# NixieClock.net
KiCad netlist of a schematic drawn in EAGLE
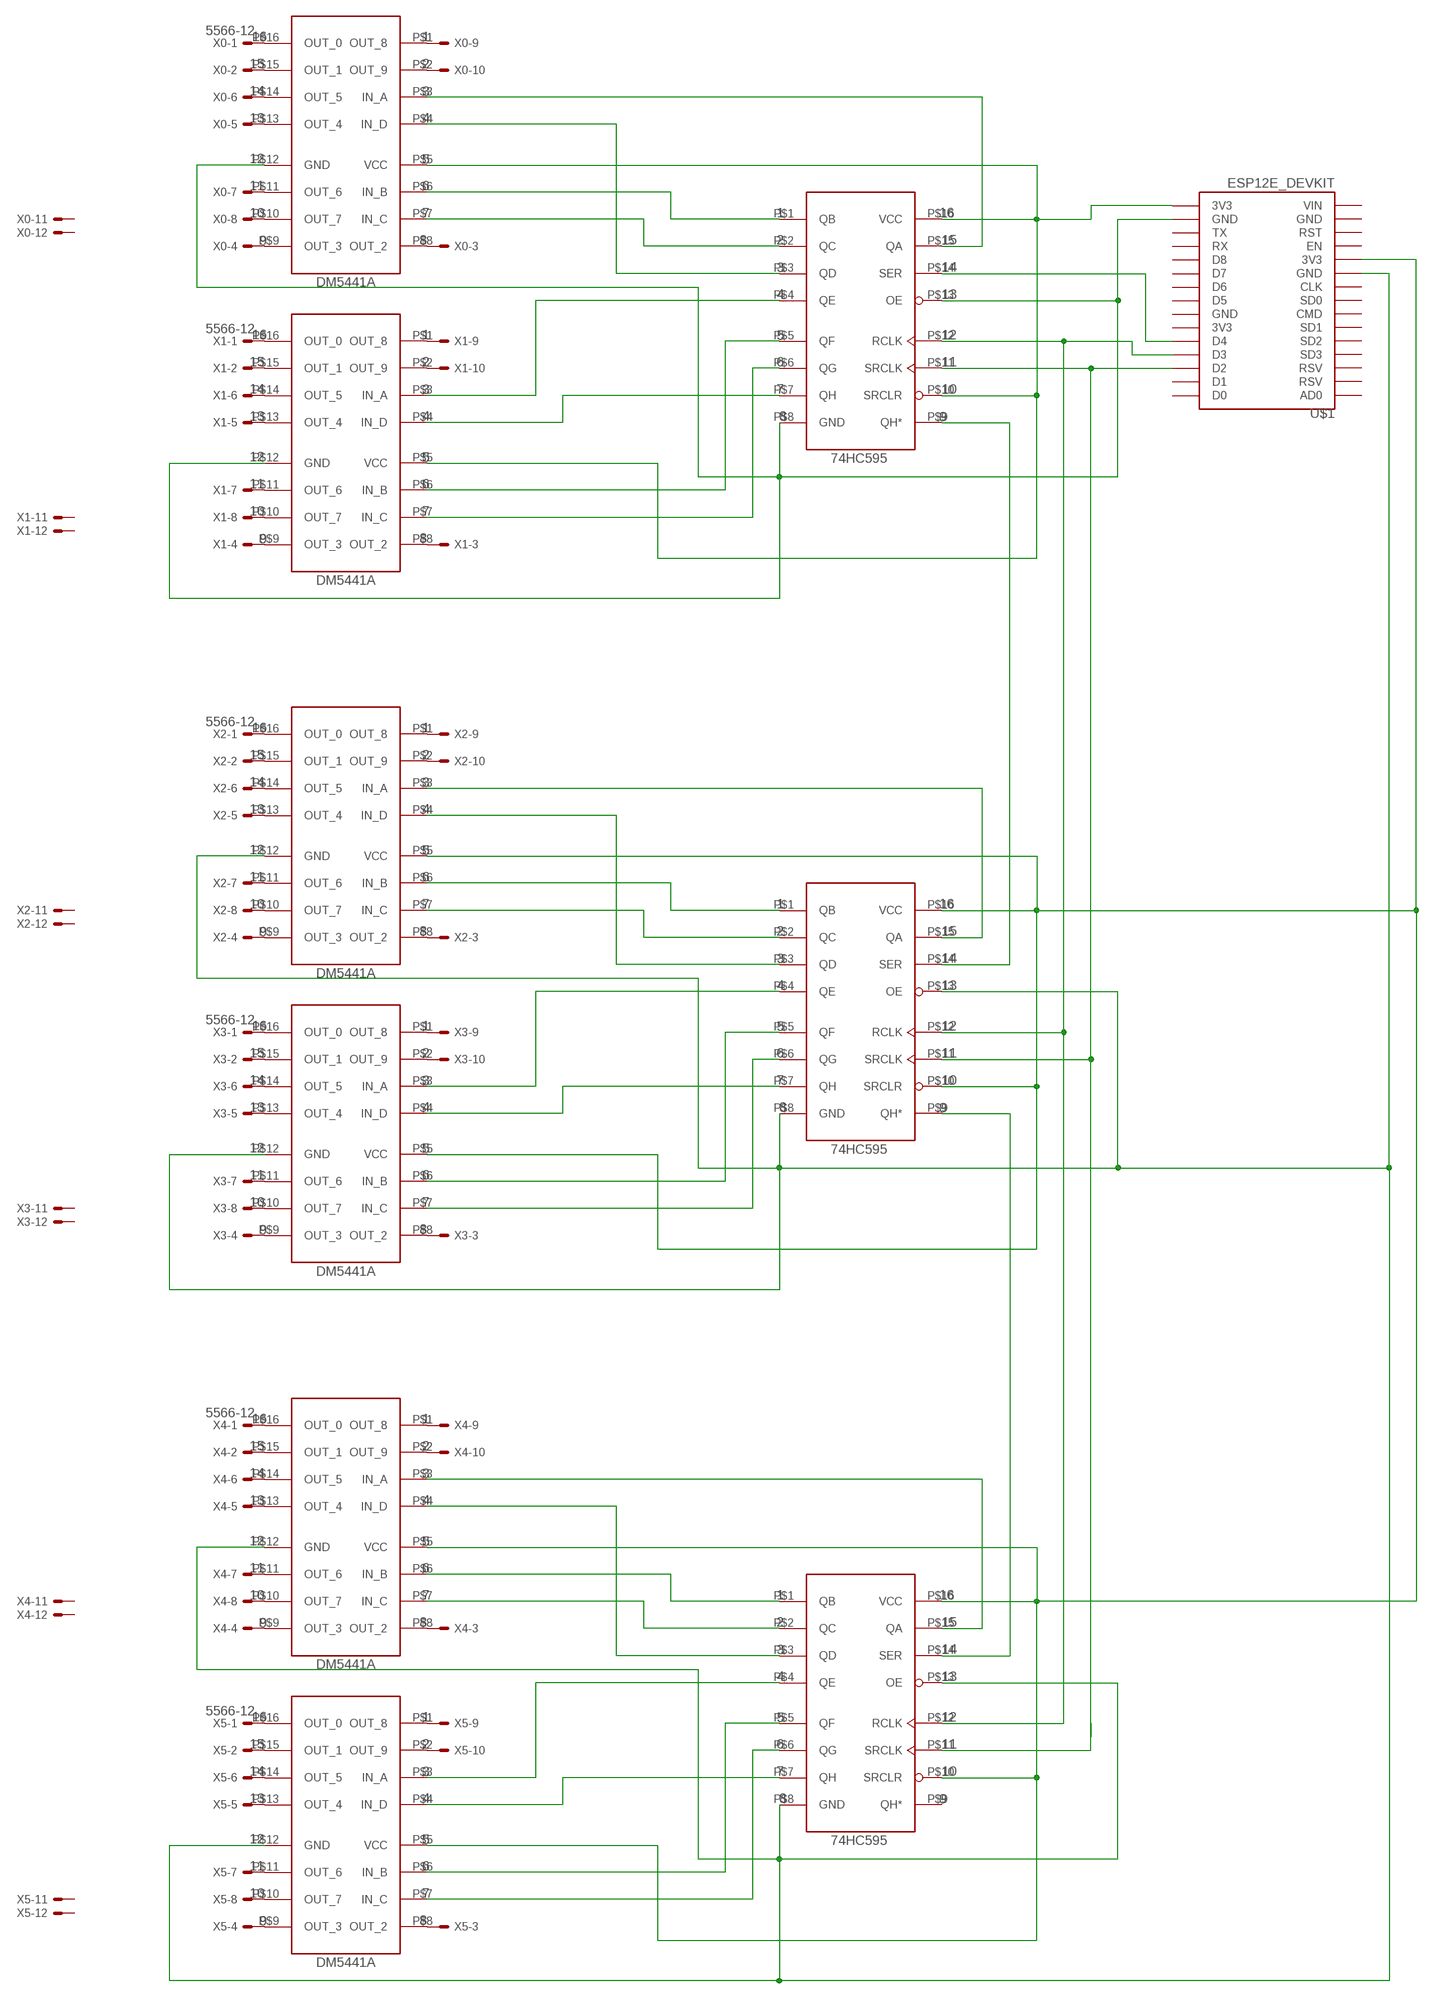
[diagram p0: schematic, sheet 1]

(export (version "E")
  (design (tool "Eeschema 10.0.6"))
  (components
    (comp (ref "BCD0")
      (value "DM5441ADIP-16")
      (footprint "eagle-import:DIP-16")
      (fields (field (name "MF") "Texas Instruments") (field (name "MP") "SN74HC595N"))
      (libsource (lib "eagle-import") (part "DM5441ADIP-16"))
    )
    (comp (ref "BCD1")
      (value "DM5441ADIP-16")
      (footprint "eagle-import:DIP-16")
      (fields (field (name "MF") "Texas Instruments") (field (name "MP") "SN74HC595N"))
      (libsource (lib "eagle-import") (part "DM5441ADIP-16"))
    )
    (comp (ref "BCD2")
      (value "DM5441ADIP-16")
      (footprint "eagle-import:DIP-16")
      (fields (field (name "MF") "Texas Instruments") (field (name "MP") "SN74HC595N"))
      (libsource (lib "eagle-import") (part "DM5441ADIP-16"))
    )
    (comp (ref "BCD3")
      (value "DM5441ADIP-16")
      (footprint "eagle-import:DIP-16")
      (fields (field (name "MF") "Texas Instruments") (field (name "MP") "SN74HC595N"))
      (libsource (lib "eagle-import") (part "DM5441ADIP-16"))
    )
    (comp (ref "BCD4")
      (value "DM5441ADIP-16")
      (footprint "eagle-import:DIP-16")
      (fields (field (name "MF") "Texas Instruments") (field (name "MP") "SN74HC595N"))
      (libsource (lib "eagle-import") (part "DM5441ADIP-16"))
    )
    (comp (ref "BCD5")
      (value "DM5441ADIP-16")
      (footprint "eagle-import:DIP-16")
      (fields (field (name "MF") "Texas Instruments") (field (name "MP") "SN74HC595N"))
      (libsource (lib "eagle-import") (part "DM5441ADIP-16"))
    )
    (comp (ref "SR0")
      (value "SN74HC595NDIP-16")
      (footprint "eagle-import:DIP-16")
      (fields (field (name "MF") "Texas Instruments") (field (name "MP") "SN74HC595N"))
      (libsource (lib "eagle-import") (part "SN74HC595NDIP-16"))
    )
    (comp (ref "SR1")
      (value "SN74HC595NDIP-16")
      (footprint "eagle-import:DIP-16")
      (fields (field (name "MF") "Texas Instruments") (field (name "MP") "SN74HC595N"))
      (libsource (lib "eagle-import") (part "SN74HC595NDIP-16"))
    )
    (comp (ref "SR2")
      (value "SN74HC595NDIP-16")
      (footprint "eagle-import:DIP-16")
      (fields (field (name "MF") "Texas Instruments") (field (name "MP") "SN74HC595N"))
      (libsource (lib "eagle-import") (part "SN74HC595NDIP-16"))
    )
    (comp (ref "U$1")
      (value "ESP12E_DEVKIT")
      (footprint "eagle-import:ESP12E_DEVKIT")
      (libsource (lib "eagle-import") (part "ESP12E_DEVKIT"))
    )
    (comp (ref "X0")
      (value "5566-12")
      (footprint "eagle-import:5566-12")
      (fields (field (name "MF") "MOLEX"))
      (libsource (lib "eagle-import") (part "5566-12"))
    )
    (comp (ref "X1")
      (value "5566-12")
      (footprint "eagle-import:5566-12")
      (fields (field (name "MF") "MOLEX"))
      (libsource (lib "eagle-import") (part "5566-12"))
    )
    (comp (ref "X2")
      (value "5566-12")
      (footprint "eagle-import:5566-12")
      (fields (field (name "MF") "MOLEX"))
      (libsource (lib "eagle-import") (part "5566-12"))
    )
    (comp (ref "X3")
      (value "5566-12")
      (footprint "eagle-import:5566-12")
      (fields (field (name "MF") "MOLEX"))
      (libsource (lib "eagle-import") (part "5566-12"))
    )
    (comp (ref "X4")
      (value "5566-12")
      (footprint "eagle-import:5566-12")
      (fields (field (name "MF") "MOLEX"))
      (libsource (lib "eagle-import") (part "5566-12"))
    )
    (comp (ref "X5")
      (value "5566-12")
      (footprint "eagle-import:5566-12")
      (fields (field (name "MF") "MOLEX"))
      (libsource (lib "eagle-import") (part "5566-12"))
    )
  )
  (nets
    (net (code "1") (name "Net-(BCD0-GND)") (class "Default")
      (node (ref "BCD0") (pin "P$12") (pinfunction "GND_P$12") (pintype "input"))
      (node (ref "BCD1") (pin "P$12") (pinfunction "GND_P$12") (pintype "input"))
      (node (ref "SR0") (pin "P$13") (pinfunction "OE_P$13") (pintype "bidirectional"))
      (node (ref "SR0") (pin "P$8") (pinfunction "GND_P$8") (pintype "bidirectional"))
      (node (ref "U$1") (pin "GND@3") (pinfunction "GND_GND@3") (pintype "bidirectional"))
    )
    (net (code "2") (name "Net-(BCD0-IN_A)") (class "Default")
      (node (ref "BCD0") (pin "P$3") (pinfunction "IN_A_P$3") (pintype "bidirectional"))
      (node (ref "SR0") (pin "P$15") (pinfunction "QA_P$15") (pintype "bidirectional"))
    )
    (net (code "3") (name "Net-(BCD0-IN_B)") (class "Default")
      (node (ref "BCD0") (pin "P$6") (pinfunction "IN_B_P$6") (pintype "bidirectional"))
      (node (ref "SR0") (pin "P$1") (pinfunction "QB_P$1") (pintype "bidirectional"))
    )
    (net (code "4") (name "Net-(BCD0-IN_C)") (class "Default")
      (node (ref "BCD0") (pin "P$7") (pinfunction "IN_C_P$7") (pintype "bidirectional"))
      (node (ref "SR0") (pin "P$2") (pinfunction "QC_P$2") (pintype "bidirectional"))
    )
    (net (code "5") (name "Net-(BCD0-IN_D)") (class "Default")
      (node (ref "BCD0") (pin "P$4") (pinfunction "IN_D_P$4") (pintype "bidirectional"))
      (node (ref "SR0") (pin "P$3") (pinfunction "QD_P$3") (pintype "bidirectional"))
    )
    (net (code "6") (name "Net-(BCD0-OUT_0)") (class "Default")
      (node (ref "BCD0") (pin "P$16") (pinfunction "OUT_0_P$16") (pintype "bidirectional"))
      (node (ref "X0") (pin "1") (pinfunction "S_1") (pintype "passive"))
    )
    (net (code "7") (name "Net-(BCD0-OUT_1)") (class "Default")
      (node (ref "BCD0") (pin "P$15") (pinfunction "OUT_1_P$15") (pintype "bidirectional"))
      (node (ref "X0") (pin "2") (pinfunction "S_2") (pintype "passive"))
    )
    (net (code "8") (name "Net-(BCD0-OUT_2)") (class "Default")
      (node (ref "BCD0") (pin "P$8") (pinfunction "OUT_2_P$8") (pintype "bidirectional"))
      (node (ref "X0") (pin "3") (pinfunction "S_3") (pintype "passive"))
    )
    (net (code "9") (name "Net-(BCD0-OUT_3)") (class "Default")
      (node (ref "BCD0") (pin "P$9") (pinfunction "OUT_3_P$9") (pintype "bidirectional"))
      (node (ref "X0") (pin "4") (pinfunction "S_4") (pintype "passive"))
    )
    (net (code "10") (name "Net-(BCD0-OUT_4)") (class "Default")
      (node (ref "BCD0") (pin "P$13") (pinfunction "OUT_4_P$13") (pintype "bidirectional"))
      (node (ref "X0") (pin "5") (pinfunction "S_5") (pintype "passive"))
    )
    (net (code "11") (name "Net-(BCD0-OUT_5)") (class "Default")
      (node (ref "BCD0") (pin "P$14") (pinfunction "OUT_5_P$14") (pintype "bidirectional"))
      (node (ref "X0") (pin "6") (pinfunction "S_6") (pintype "passive"))
    )
    (net (code "12") (name "Net-(BCD0-OUT_6)") (class "Default")
      (node (ref "BCD0") (pin "P$11") (pinfunction "OUT_6_P$11") (pintype "bidirectional"))
      (node (ref "X0") (pin "7") (pinfunction "S_7") (pintype "passive"))
    )
    (net (code "13") (name "Net-(BCD0-OUT_7)") (class "Default")
      (node (ref "BCD0") (pin "P$10") (pinfunction "OUT_7_P$10") (pintype "bidirectional"))
      (node (ref "X0") (pin "8") (pinfunction "S_8") (pintype "passive"))
    )
    (net (code "14") (name "Net-(BCD0-OUT_8)") (class "Default")
      (node (ref "BCD0") (pin "P$1") (pinfunction "OUT_8_P$1") (pintype "bidirectional"))
      (node (ref "X0") (pin "9") (pinfunction "S_9") (pintype "passive"))
    )
    (net (code "15") (name "Net-(BCD0-OUT_9)") (class "Default")
      (node (ref "BCD0") (pin "P$2") (pinfunction "OUT_9_P$2") (pintype "bidirectional"))
      (node (ref "X0") (pin "10") (pinfunction "S_10") (pintype "passive"))
    )
    (net (code "16") (name "Net-(BCD0-VCC)") (class "Default")
      (node (ref "BCD0") (pin "P$5") (pinfunction "VCC_P$5") (pintype "bidirectional"))
      (node (ref "BCD1") (pin "P$5") (pinfunction "VCC_P$5") (pintype "bidirectional"))
      (node (ref "SR0") (pin "P$10") (pinfunction "SRCLR_P$10") (pintype "bidirectional"))
      (node (ref "SR0") (pin "P$16") (pinfunction "VCC_P$16") (pintype "bidirectional"))
      (node (ref "U$1") (pin "3V3@2") (pinfunction "3V3_3V3@2") (pintype "bidirectional"))
    )
    (net (code "17") (name "Net-(BCD1-IN_A)") (class "Default")
      (node (ref "BCD1") (pin "P$3") (pinfunction "IN_A_P$3") (pintype "bidirectional"))
      (node (ref "SR0") (pin "P$4") (pinfunction "QE_P$4") (pintype "bidirectional"))
    )
    (net (code "18") (name "Net-(BCD1-IN_B)") (class "Default")
      (node (ref "BCD1") (pin "P$6") (pinfunction "IN_B_P$6") (pintype "bidirectional"))
      (node (ref "SR0") (pin "P$5") (pinfunction "QF_P$5") (pintype "bidirectional"))
    )
    (net (code "19") (name "Net-(BCD1-IN_C)") (class "Default")
      (node (ref "BCD1") (pin "P$7") (pinfunction "IN_C_P$7") (pintype "bidirectional"))
      (node (ref "SR0") (pin "P$6") (pinfunction "QG_P$6") (pintype "bidirectional"))
    )
    (net (code "20") (name "Net-(BCD1-IN_D)") (class "Default")
      (node (ref "BCD1") (pin "P$4") (pinfunction "IN_D_P$4") (pintype "bidirectional"))
      (node (ref "SR0") (pin "P$7") (pinfunction "QH_P$7") (pintype "bidirectional"))
    )
    (net (code "21") (name "Net-(BCD1-OUT_0)") (class "Default")
      (node (ref "BCD1") (pin "P$16") (pinfunction "OUT_0_P$16") (pintype "bidirectional"))
      (node (ref "X1") (pin "1") (pinfunction "S_1") (pintype "passive"))
    )
    (net (code "22") (name "Net-(BCD1-OUT_1)") (class "Default")
      (node (ref "BCD1") (pin "P$15") (pinfunction "OUT_1_P$15") (pintype "bidirectional"))
      (node (ref "X1") (pin "2") (pinfunction "S_2") (pintype "passive"))
    )
    (net (code "23") (name "Net-(BCD1-OUT_2)") (class "Default")
      (node (ref "BCD1") (pin "P$8") (pinfunction "OUT_2_P$8") (pintype "bidirectional"))
      (node (ref "X1") (pin "3") (pinfunction "S_3") (pintype "passive"))
    )
    (net (code "24") (name "Net-(BCD1-OUT_3)") (class "Default")
      (node (ref "BCD1") (pin "P$9") (pinfunction "OUT_3_P$9") (pintype "bidirectional"))
      (node (ref "X1") (pin "4") (pinfunction "S_4") (pintype "passive"))
    )
    (net (code "25") (name "Net-(BCD1-OUT_4)") (class "Default")
      (node (ref "BCD1") (pin "P$13") (pinfunction "OUT_4_P$13") (pintype "bidirectional"))
      (node (ref "X1") (pin "5") (pinfunction "S_5") (pintype "passive"))
    )
    (net (code "26") (name "Net-(BCD1-OUT_5)") (class "Default")
      (node (ref "BCD1") (pin "P$14") (pinfunction "OUT_5_P$14") (pintype "bidirectional"))
      (node (ref "X1") (pin "6") (pinfunction "S_6") (pintype "passive"))
    )
    (net (code "27") (name "Net-(BCD1-OUT_6)") (class "Default")
      (node (ref "BCD1") (pin "P$11") (pinfunction "OUT_6_P$11") (pintype "bidirectional"))
      (node (ref "X1") (pin "7") (pinfunction "S_7") (pintype "passive"))
    )
    (net (code "28") (name "Net-(BCD1-OUT_7)") (class "Default")
      (node (ref "BCD1") (pin "P$10") (pinfunction "OUT_7_P$10") (pintype "bidirectional"))
      (node (ref "X1") (pin "8") (pinfunction "S_8") (pintype "passive"))
    )
    (net (code "29") (name "Net-(BCD1-OUT_8)") (class "Default")
      (node (ref "BCD1") (pin "P$1") (pinfunction "OUT_8_P$1") (pintype "bidirectional"))
      (node (ref "X1") (pin "9") (pinfunction "S_9") (pintype "passive"))
    )
    (net (code "30") (name "Net-(BCD1-OUT_9)") (class "Default")
      (node (ref "BCD1") (pin "P$2") (pinfunction "OUT_9_P$2") (pintype "bidirectional"))
      (node (ref "X1") (pin "10") (pinfunction "S_10") (pintype "passive"))
    )
    (net (code "31") (name "Net-(BCD2-GND)") (class "Default")
      (node (ref "BCD2") (pin "P$12") (pinfunction "GND_P$12") (pintype "input"))
      (node (ref "BCD3") (pin "P$12") (pinfunction "GND_P$12") (pintype "input"))
      (node (ref "BCD4") (pin "P$12") (pinfunction "GND_P$12") (pintype "input"))
      (node (ref "BCD5") (pin "P$12") (pinfunction "GND_P$12") (pintype "input"))
      (node (ref "SR1") (pin "P$13") (pinfunction "OE_P$13") (pintype "bidirectional"))
      (node (ref "SR1") (pin "P$8") (pinfunction "GND_P$8") (pintype "bidirectional"))
      (node (ref "SR2") (pin "P$13") (pinfunction "OE_P$13") (pintype "bidirectional"))
      (node (ref "SR2") (pin "P$8") (pinfunction "GND_P$8") (pintype "bidirectional"))
      (node (ref "U$1") (pin "GND@0") (pinfunction "GND_GND@0") (pintype "bidirectional"))
    )
    (net (code "32") (name "Net-(BCD2-IN_A)") (class "Default")
      (node (ref "BCD2") (pin "P$3") (pinfunction "IN_A_P$3") (pintype "bidirectional"))
      (node (ref "SR1") (pin "P$15") (pinfunction "QA_P$15") (pintype "bidirectional"))
    )
    (net (code "33") (name "Net-(BCD2-IN_B)") (class "Default")
      (node (ref "BCD2") (pin "P$6") (pinfunction "IN_B_P$6") (pintype "bidirectional"))
      (node (ref "SR1") (pin "P$1") (pinfunction "QB_P$1") (pintype "bidirectional"))
    )
    (net (code "34") (name "Net-(BCD2-IN_C)") (class "Default")
      (node (ref "BCD2") (pin "P$7") (pinfunction "IN_C_P$7") (pintype "bidirectional"))
      (node (ref "SR1") (pin "P$2") (pinfunction "QC_P$2") (pintype "bidirectional"))
    )
    (net (code "35") (name "Net-(BCD2-IN_D)") (class "Default")
      (node (ref "BCD2") (pin "P$4") (pinfunction "IN_D_P$4") (pintype "bidirectional"))
      (node (ref "SR1") (pin "P$3") (pinfunction "QD_P$3") (pintype "bidirectional"))
    )
    (net (code "36") (name "Net-(BCD2-OUT_0)") (class "Default")
      (node (ref "BCD2") (pin "P$16") (pinfunction "OUT_0_P$16") (pintype "bidirectional"))
      (node (ref "X2") (pin "1") (pinfunction "S_1") (pintype "passive"))
    )
    (net (code "37") (name "Net-(BCD2-OUT_1)") (class "Default")
      (node (ref "BCD2") (pin "P$15") (pinfunction "OUT_1_P$15") (pintype "bidirectional"))
      (node (ref "X2") (pin "2") (pinfunction "S_2") (pintype "passive"))
    )
    (net (code "38") (name "Net-(BCD2-OUT_2)") (class "Default")
      (node (ref "BCD2") (pin "P$8") (pinfunction "OUT_2_P$8") (pintype "bidirectional"))
      (node (ref "X2") (pin "3") (pinfunction "S_3") (pintype "passive"))
    )
    (net (code "39") (name "Net-(BCD2-OUT_3)") (class "Default")
      (node (ref "BCD2") (pin "P$9") (pinfunction "OUT_3_P$9") (pintype "bidirectional"))
      (node (ref "X2") (pin "4") (pinfunction "S_4") (pintype "passive"))
    )
    (net (code "40") (name "Net-(BCD2-OUT_4)") (class "Default")
      (node (ref "BCD2") (pin "P$13") (pinfunction "OUT_4_P$13") (pintype "bidirectional"))
      (node (ref "X2") (pin "5") (pinfunction "S_5") (pintype "passive"))
    )
    (net (code "41") (name "Net-(BCD2-OUT_5)") (class "Default")
      (node (ref "BCD2") (pin "P$14") (pinfunction "OUT_5_P$14") (pintype "bidirectional"))
      (node (ref "X2") (pin "6") (pinfunction "S_6") (pintype "passive"))
    )
    (net (code "42") (name "Net-(BCD2-OUT_6)") (class "Default")
      (node (ref "BCD2") (pin "P$11") (pinfunction "OUT_6_P$11") (pintype "bidirectional"))
      (node (ref "X2") (pin "7") (pinfunction "S_7") (pintype "passive"))
    )
    (net (code "43") (name "Net-(BCD2-OUT_7)") (class "Default")
      (node (ref "BCD2") (pin "P$10") (pinfunction "OUT_7_P$10") (pintype "bidirectional"))
      (node (ref "X2") (pin "8") (pinfunction "S_8") (pintype "passive"))
    )
    (net (code "44") (name "Net-(BCD2-OUT_8)") (class "Default")
      (node (ref "BCD2") (pin "P$1") (pinfunction "OUT_8_P$1") (pintype "bidirectional"))
      (node (ref "X2") (pin "9") (pinfunction "S_9") (pintype "passive"))
    )
    (net (code "45") (name "Net-(BCD2-OUT_9)") (class "Default")
      (node (ref "BCD2") (pin "P$2") (pinfunction "OUT_9_P$2") (pintype "bidirectional"))
      (node (ref "X2") (pin "10") (pinfunction "S_10") (pintype "passive"))
    )
    (net (code "46") (name "Net-(BCD2-VCC)") (class "Default")
      (node (ref "BCD2") (pin "P$5") (pinfunction "VCC_P$5") (pintype "bidirectional"))
      (node (ref "BCD3") (pin "P$5") (pinfunction "VCC_P$5") (pintype "bidirectional"))
      (node (ref "BCD4") (pin "P$5") (pinfunction "VCC_P$5") (pintype "bidirectional"))
      (node (ref "BCD5") (pin "P$5") (pinfunction "VCC_P$5") (pintype "bidirectional"))
      (node (ref "SR1") (pin "P$10") (pinfunction "SRCLR_P$10") (pintype "bidirectional"))
      (node (ref "SR1") (pin "P$16") (pinfunction "VCC_P$16") (pintype "bidirectional"))
      (node (ref "SR2") (pin "P$10") (pinfunction "SRCLR_P$10") (pintype "bidirectional"))
      (node (ref "SR2") (pin "P$16") (pinfunction "VCC_P$16") (pintype "bidirectional"))
      (node (ref "U$1") (pin "3V3@0") (pinfunction "3V3_3V3@0") (pintype "bidirectional"))
    )
    (net (code "47") (name "Net-(BCD3-IN_A)") (class "Default")
      (node (ref "BCD3") (pin "P$3") (pinfunction "IN_A_P$3") (pintype "bidirectional"))
      (node (ref "SR1") (pin "P$4") (pinfunction "QE_P$4") (pintype "bidirectional"))
    )
    (net (code "48") (name "Net-(BCD3-IN_B)") (class "Default")
      (node (ref "BCD3") (pin "P$6") (pinfunction "IN_B_P$6") (pintype "bidirectional"))
      (node (ref "SR1") (pin "P$5") (pinfunction "QF_P$5") (pintype "bidirectional"))
    )
    (net (code "49") (name "Net-(BCD3-IN_C)") (class "Default")
      (node (ref "BCD3") (pin "P$7") (pinfunction "IN_C_P$7") (pintype "bidirectional"))
      (node (ref "SR1") (pin "P$6") (pinfunction "QG_P$6") (pintype "bidirectional"))
    )
    (net (code "50") (name "Net-(BCD3-IN_D)") (class "Default")
      (node (ref "BCD3") (pin "P$4") (pinfunction "IN_D_P$4") (pintype "bidirectional"))
      (node (ref "SR1") (pin "P$7") (pinfunction "QH_P$7") (pintype "bidirectional"))
    )
    (net (code "51") (name "Net-(BCD3-OUT_0)") (class "Default")
      (node (ref "BCD3") (pin "P$16") (pinfunction "OUT_0_P$16") (pintype "bidirectional"))
      (node (ref "X3") (pin "1") (pinfunction "S_1") (pintype "passive"))
    )
    (net (code "52") (name "Net-(BCD3-OUT_1)") (class "Default")
      (node (ref "BCD3") (pin "P$15") (pinfunction "OUT_1_P$15") (pintype "bidirectional"))
      (node (ref "X3") (pin "2") (pinfunction "S_2") (pintype "passive"))
    )
    (net (code "53") (name "Net-(BCD3-OUT_2)") (class "Default")
      (node (ref "BCD3") (pin "P$8") (pinfunction "OUT_2_P$8") (pintype "bidirectional"))
      (node (ref "X3") (pin "3") (pinfunction "S_3") (pintype "passive"))
    )
    (net (code "54") (name "Net-(BCD3-OUT_3)") (class "Default")
      (node (ref "BCD3") (pin "P$9") (pinfunction "OUT_3_P$9") (pintype "bidirectional"))
      (node (ref "X3") (pin "4") (pinfunction "S_4") (pintype "passive"))
    )
    (net (code "55") (name "Net-(BCD3-OUT_4)") (class "Default")
      (node (ref "BCD3") (pin "P$13") (pinfunction "OUT_4_P$13") (pintype "bidirectional"))
      (node (ref "X3") (pin "5") (pinfunction "S_5") (pintype "passive"))
    )
    (net (code "56") (name "Net-(BCD3-OUT_5)") (class "Default")
      (node (ref "BCD3") (pin "P$14") (pinfunction "OUT_5_P$14") (pintype "bidirectional"))
      (node (ref "X3") (pin "6") (pinfunction "S_6") (pintype "passive"))
    )
    (net (code "57") (name "Net-(BCD3-OUT_6)") (class "Default")
      (node (ref "BCD3") (pin "P$11") (pinfunction "OUT_6_P$11") (pintype "bidirectional"))
      (node (ref "X3") (pin "7") (pinfunction "S_7") (pintype "passive"))
    )
    (net (code "58") (name "Net-(BCD3-OUT_7)") (class "Default")
      (node (ref "BCD3") (pin "P$10") (pinfunction "OUT_7_P$10") (pintype "bidirectional"))
      (node (ref "X3") (pin "8") (pinfunction "S_8") (pintype "passive"))
    )
    (net (code "59") (name "Net-(BCD3-OUT_8)") (class "Default")
      (node (ref "BCD3") (pin "P$1") (pinfunction "OUT_8_P$1") (pintype "bidirectional"))
      (node (ref "X3") (pin "9") (pinfunction "S_9") (pintype "passive"))
    )
    (net (code "60") (name "Net-(BCD3-OUT_9)") (class "Default")
      (node (ref "BCD3") (pin "P$2") (pinfunction "OUT_9_P$2") (pintype "bidirectional"))
      (node (ref "X3") (pin "10") (pinfunction "S_10") (pintype "passive"))
    )
    (net (code "61") (name "Net-(BCD4-IN_A)") (class "Default")
      (node (ref "BCD4") (pin "P$3") (pinfunction "IN_A_P$3") (pintype "bidirectional"))
      (node (ref "SR2") (pin "P$15") (pinfunction "QA_P$15") (pintype "bidirectional"))
    )
    (net (code "62") (name "Net-(BCD4-IN_B)") (class "Default")
      (node (ref "BCD4") (pin "P$6") (pinfunction "IN_B_P$6") (pintype "bidirectional"))
      (node (ref "SR2") (pin "P$1") (pinfunction "QB_P$1") (pintype "bidirectional"))
    )
    (net (code "63") (name "Net-(BCD4-IN_C)") (class "Default")
      (node (ref "BCD4") (pin "P$7") (pinfunction "IN_C_P$7") (pintype "bidirectional"))
      (node (ref "SR2") (pin "P$2") (pinfunction "QC_P$2") (pintype "bidirectional"))
    )
    (net (code "64") (name "Net-(BCD4-IN_D)") (class "Default")
      (node (ref "BCD4") (pin "P$4") (pinfunction "IN_D_P$4") (pintype "bidirectional"))
      (node (ref "SR2") (pin "P$3") (pinfunction "QD_P$3") (pintype "bidirectional"))
    )
    (net (code "65") (name "Net-(BCD4-OUT_0)") (class "Default")
      (node (ref "BCD4") (pin "P$16") (pinfunction "OUT_0_P$16") (pintype "bidirectional"))
      (node (ref "X4") (pin "1") (pinfunction "S_1") (pintype "passive"))
    )
    (net (code "66") (name "Net-(BCD4-OUT_1)") (class "Default")
      (node (ref "BCD4") (pin "P$15") (pinfunction "OUT_1_P$15") (pintype "bidirectional"))
      (node (ref "X4") (pin "2") (pinfunction "S_2") (pintype "passive"))
    )
    (net (code "67") (name "Net-(BCD4-OUT_2)") (class "Default")
      (node (ref "BCD4") (pin "P$8") (pinfunction "OUT_2_P$8") (pintype "bidirectional"))
      (node (ref "X4") (pin "3") (pinfunction "S_3") (pintype "passive"))
    )
    (net (code "68") (name "Net-(BCD4-OUT_3)") (class "Default")
      (node (ref "BCD4") (pin "P$9") (pinfunction "OUT_3_P$9") (pintype "bidirectional"))
      (node (ref "X4") (pin "4") (pinfunction "S_4") (pintype "passive"))
    )
    (net (code "69") (name "Net-(BCD4-OUT_4)") (class "Default")
      (node (ref "BCD4") (pin "P$13") (pinfunction "OUT_4_P$13") (pintype "bidirectional"))
      (node (ref "X4") (pin "5") (pinfunction "S_5") (pintype "passive"))
    )
    (net (code "70") (name "Net-(BCD4-OUT_5)") (class "Default")
      (node (ref "BCD4") (pin "P$14") (pinfunction "OUT_5_P$14") (pintype "bidirectional"))
      (node (ref "X4") (pin "6") (pinfunction "S_6") (pintype "passive"))
    )
    (net (code "71") (name "Net-(BCD4-OUT_6)") (class "Default")
      (node (ref "BCD4") (pin "P$11") (pinfunction "OUT_6_P$11") (pintype "bidirectional"))
      (node (ref "X4") (pin "7") (pinfunction "S_7") (pintype "passive"))
    )
    (net (code "72") (name "Net-(BCD4-OUT_7)") (class "Default")
      (node (ref "BCD4") (pin "P$10") (pinfunction "OUT_7_P$10") (pintype "bidirectional"))
      (node (ref "X4") (pin "8") (pinfunction "S_8") (pintype "passive"))
    )
    (net (code "73") (name "Net-(BCD4-OUT_8)") (class "Default")
      (node (ref "BCD4") (pin "P$1") (pinfunction "OUT_8_P$1") (pintype "bidirectional"))
      (node (ref "X4") (pin "9") (pinfunction "S_9") (pintype "passive"))
    )
    (net (code "74") (name "Net-(BCD4-OUT_9)") (class "Default")
      (node (ref "BCD4") (pin "P$2") (pinfunction "OUT_9_P$2") (pintype "bidirectional"))
      (node (ref "X4") (pin "10") (pinfunction "S_10") (pintype "passive"))
    )
    (net (code "75") (name "Net-(BCD5-IN_A)") (class "Default")
      (node (ref "BCD5") (pin "P$3") (pinfunction "IN_A_P$3") (pintype "bidirectional"))
      (node (ref "SR2") (pin "P$4") (pinfunction "QE_P$4") (pintype "bidirectional"))
    )
    (net (code "76") (name "Net-(BCD5-IN_B)") (class "Default")
      (node (ref "BCD5") (pin "P$6") (pinfunction "IN_B_P$6") (pintype "bidirectional"))
      (node (ref "SR2") (pin "P$5") (pinfunction "QF_P$5") (pintype "bidirectional"))
    )
    (net (code "77") (name "Net-(BCD5-IN_C)") (class "Default")
      (node (ref "BCD5") (pin "P$7") (pinfunction "IN_C_P$7") (pintype "bidirectional"))
      (node (ref "SR2") (pin "P$6") (pinfunction "QG_P$6") (pintype "bidirectional"))
    )
    (net (code "78") (name "Net-(BCD5-IN_D)") (class "Default")
      (node (ref "BCD5") (pin "P$4") (pinfunction "IN_D_P$4") (pintype "bidirectional"))
      (node (ref "SR2") (pin "P$7") (pinfunction "QH_P$7") (pintype "bidirectional"))
    )
    (net (code "79") (name "Net-(BCD5-OUT_0)") (class "Default")
      (node (ref "BCD5") (pin "P$16") (pinfunction "OUT_0_P$16") (pintype "bidirectional"))
      (node (ref "X5") (pin "1") (pinfunction "S_1") (pintype "passive"))
    )
    (net (code "80") (name "Net-(BCD5-OUT_1)") (class "Default")
      (node (ref "BCD5") (pin "P$15") (pinfunction "OUT_1_P$15") (pintype "bidirectional"))
      (node (ref "X5") (pin "2") (pinfunction "S_2") (pintype "passive"))
    )
    (net (code "81") (name "Net-(BCD5-OUT_2)") (class "Default")
      (node (ref "BCD5") (pin "P$8") (pinfunction "OUT_2_P$8") (pintype "bidirectional"))
      (node (ref "X5") (pin "3") (pinfunction "S_3") (pintype "passive"))
    )
    (net (code "82") (name "Net-(BCD5-OUT_3)") (class "Default")
      (node (ref "BCD5") (pin "P$9") (pinfunction "OUT_3_P$9") (pintype "bidirectional"))
      (node (ref "X5") (pin "4") (pinfunction "S_4") (pintype "passive"))
    )
    (net (code "83") (name "Net-(BCD5-OUT_4)") (class "Default")
      (node (ref "BCD5") (pin "P$13") (pinfunction "OUT_4_P$13") (pintype "bidirectional"))
      (node (ref "X5") (pin "5") (pinfunction "S_5") (pintype "passive"))
    )
    (net (code "84") (name "Net-(BCD5-OUT_5)") (class "Default")
      (node (ref "BCD5") (pin "P$14") (pinfunction "OUT_5_P$14") (pintype "bidirectional"))
      (node (ref "X5") (pin "6") (pinfunction "S_6") (pintype "passive"))
    )
    (net (code "85") (name "Net-(BCD5-OUT_6)") (class "Default")
      (node (ref "BCD5") (pin "P$11") (pinfunction "OUT_6_P$11") (pintype "bidirectional"))
      (node (ref "X5") (pin "7") (pinfunction "S_7") (pintype "passive"))
    )
    (net (code "86") (name "Net-(BCD5-OUT_7)") (class "Default")
      (node (ref "BCD5") (pin "P$10") (pinfunction "OUT_7_P$10") (pintype "bidirectional"))
      (node (ref "X5") (pin "8") (pinfunction "S_8") (pintype "passive"))
    )
    (net (code "87") (name "Net-(BCD5-OUT_8)") (class "Default")
      (node (ref "BCD5") (pin "P$1") (pinfunction "OUT_8_P$1") (pintype "bidirectional"))
      (node (ref "X5") (pin "9") (pinfunction "S_9") (pintype "passive"))
    )
    (net (code "88") (name "Net-(BCD5-OUT_9)") (class "Default")
      (node (ref "BCD5") (pin "P$2") (pinfunction "OUT_9_P$2") (pintype "bidirectional"))
      (node (ref "X5") (pin "10") (pinfunction "S_10") (pintype "passive"))
    )
    (net (code "89") (name "Net-(SR0-QH*)") (class "Default")
      (node (ref "SR0") (pin "P$9") (pinfunction "QH*_P$9") (pintype "bidirectional"))
      (node (ref "SR1") (pin "P$14") (pinfunction "SER_P$14") (pintype "bidirectional"))
    )
    (net (code "90") (name "Net-(SR0-RCLK)") (class "Default")
      (node (ref "SR0") (pin "P$12") (pinfunction "RCLK_P$12") (pintype "input"))
      (node (ref "SR1") (pin "P$12") (pinfunction "RCLK_P$12") (pintype "input"))
      (node (ref "SR2") (pin "P$12") (pinfunction "RCLK_P$12") (pintype "input"))
      (node (ref "U$1") (pin "D3") (pinfunction "D3_D3") (pintype "bidirectional"))
    )
    (net (code "91") (name "Net-(SR0-SER)") (class "Default")
      (node (ref "SR0") (pin "P$14") (pinfunction "SER_P$14") (pintype "bidirectional"))
      (node (ref "U$1") (pin "D4") (pinfunction "D4_D4") (pintype "bidirectional"))
    )
    (net (code "92") (name "Net-(SR0-SRCLK)") (class "Default")
      (node (ref "SR0") (pin "P$11") (pinfunction "SRCLK_P$11") (pintype "bidirectional"))
      (node (ref "SR1") (pin "P$11") (pinfunction "SRCLK_P$11") (pintype "bidirectional"))
      (node (ref "SR2") (pin "P$11") (pinfunction "SRCLK_P$11") (pintype "bidirectional"))
      (node (ref "U$1") (pin "D2") (pinfunction "D2_D2") (pintype "bidirectional"))
    )
    (net (code "93") (name "Net-(SR1-QH*)") (class "Default")
      (node (ref "SR1") (pin "P$9") (pinfunction "QH*_P$9") (pintype "bidirectional"))
      (node (ref "SR2") (pin "P$14") (pinfunction "SER_P$14") (pintype "bidirectional"))
    )
    (net (code "94") (name "unconnected-(SR2-QH*-PadP$9)") (class "Default")
      (node (ref "SR2") (pin "P$9") (pinfunction "QH*_P$9") (pintype "bidirectional"))
    )
    (net (code "95") (name "unconnected-(U$1-3V3-Pad3V3@1)") (class "Default")
      (node (ref "U$1") (pin "3V3@1") (pinfunction "3V3_3V3@1") (pintype "bidirectional"))
    )
    (net (code "96") (name "unconnected-(U$1-GND-PadGND@1)") (class "Default")
      (node (ref "U$1") (pin "GND@1") (pinfunction "GND_GND@1") (pintype "bidirectional"))
    )
    (net (code "97") (name "unconnected-(U$1-GND-PadGND@2)") (class "Default")
      (node (ref "U$1") (pin "GND@2") (pinfunction "GND_GND@2") (pintype "bidirectional"))
    )
    (net (code "98") (name "unconnected-(U$1-PadAD0)") (class "Default")
      (node (ref "U$1") (pin "AD0") (pinfunction "AD0_AD0") (pintype "bidirectional"))
    )
    (net (code "99") (name "unconnected-(U$1-PadCLK)") (class "Default")
      (node (ref "U$1") (pin "CLK") (pinfunction "CLK_CLK") (pintype "bidirectional"))
    )
    (net (code "100") (name "unconnected-(U$1-PadCMD)") (class "Default")
      (node (ref "U$1") (pin "CMD") (pinfunction "CMD_CMD") (pintype "bidirectional"))
    )
    (net (code "101") (name "unconnected-(U$1-PadD0)") (class "Default")
      (node (ref "U$1") (pin "D0") (pinfunction "D0_D0") (pintype "bidirectional"))
    )
    (net (code "102") (name "unconnected-(U$1-PadD1)") (class "Default")
      (node (ref "U$1") (pin "D1") (pinfunction "D1_D1") (pintype "bidirectional"))
    )
    (net (code "103") (name "unconnected-(U$1-PadD5)") (class "Default")
      (node (ref "U$1") (pin "D5") (pinfunction "D5_D5") (pintype "bidirectional"))
    )
    (net (code "104") (name "unconnected-(U$1-PadD6)") (class "Default")
      (node (ref "U$1") (pin "D6") (pinfunction "D6_D6") (pintype "bidirectional"))
    )
    (net (code "105") (name "unconnected-(U$1-PadD7)") (class "Default")
      (node (ref "U$1") (pin "D7") (pinfunction "D7_D7") (pintype "bidirectional"))
    )
    (net (code "106") (name "unconnected-(U$1-PadD8)") (class "Default")
      (node (ref "U$1") (pin "D8") (pinfunction "D8_D8") (pintype "bidirectional"))
    )
    (net (code "107") (name "unconnected-(U$1-PadEN)") (class "Default")
      (node (ref "U$1") (pin "EN") (pinfunction "EN_EN") (pintype "bidirectional"))
    )
    (net (code "108") (name "unconnected-(U$1-PadRST)") (class "Default")
      (node (ref "U$1") (pin "RST") (pinfunction "RST_RST") (pintype "bidirectional"))
    )
    (net (code "109") (name "unconnected-(U$1-PadRX)") (class "Default")
      (node (ref "U$1") (pin "RX") (pinfunction "RX_RX") (pintype "bidirectional"))
    )
    (net (code "110") (name "unconnected-(U$1-PadSD0)") (class "Default")
      (node (ref "U$1") (pin "SD0") (pinfunction "SD0_SD0") (pintype "bidirectional"))
    )
    (net (code "111") (name "unconnected-(U$1-PadSD1)") (class "Default")
      (node (ref "U$1") (pin "SD1") (pinfunction "SD1_SD1") (pintype "bidirectional"))
    )
    (net (code "112") (name "unconnected-(U$1-PadSD2)") (class "Default")
      (node (ref "U$1") (pin "SD2") (pinfunction "SD2_SD2") (pintype "bidirectional"))
    )
    (net (code "113") (name "unconnected-(U$1-PadSD3)") (class "Default")
      (node (ref "U$1") (pin "SD3") (pinfunction "SD3_SD3") (pintype "bidirectional"))
    )
    (net (code "114") (name "unconnected-(U$1-PadTX)") (class "Default")
      (node (ref "U$1") (pin "TX") (pinfunction "TX_TX") (pintype "bidirectional"))
    )
    (net (code "115") (name "unconnected-(U$1-PadVIN)") (class "Default")
      (node (ref "U$1") (pin "VIN") (pinfunction "VIN_VIN") (pintype "bidirectional"))
    )
    (net (code "116") (name "unconnected-(U$1-RSV-PadRSV@0)") (class "Default")
      (node (ref "U$1") (pin "RSV@0") (pinfunction "RSV_RSV@0") (pintype "bidirectional"))
    )
    (net (code "117") (name "unconnected-(U$1-RSV-PadRSV@1)") (class "Default")
      (node (ref "U$1") (pin "RSV@1") (pinfunction "RSV_RSV@1") (pintype "bidirectional"))
    )
    (net (code "118") (name "unconnected-(X0C-S-Pad11)") (class "Default")
      (node (ref "X0") (pin "11") (pinfunction "S_11") (pintype "passive"))
    )
    (net (code "119") (name "unconnected-(X0D-S-Pad12)") (class "Default")
      (node (ref "X0") (pin "12") (pinfunction "S_12") (pintype "passive"))
    )
    (net (code "120") (name "unconnected-(X1C-S-Pad11)") (class "Default")
      (node (ref "X1") (pin "11") (pinfunction "S_11") (pintype "passive"))
    )
    (net (code "121") (name "unconnected-(X1D-S-Pad12)") (class "Default")
      (node (ref "X1") (pin "12") (pinfunction "S_12") (pintype "passive"))
    )
    (net (code "122") (name "unconnected-(X2C-S-Pad11)") (class "Default")
      (node (ref "X2") (pin "11") (pinfunction "S_11") (pintype "passive"))
    )
    (net (code "123") (name "unconnected-(X2D-S-Pad12)") (class "Default")
      (node (ref "X2") (pin "12") (pinfunction "S_12") (pintype "passive"))
    )
    (net (code "124") (name "unconnected-(X3C-S-Pad11)") (class "Default")
      (node (ref "X3") (pin "11") (pinfunction "S_11") (pintype "passive"))
    )
    (net (code "125") (name "unconnected-(X3D-S-Pad12)") (class "Default")
      (node (ref "X3") (pin "12") (pinfunction "S_12") (pintype "passive"))
    )
    (net (code "126") (name "unconnected-(X4C-S-Pad11)") (class "Default")
      (node (ref "X4") (pin "11") (pinfunction "S_11") (pintype "passive"))
    )
    (net (code "127") (name "unconnected-(X4D-S-Pad12)") (class "Default")
      (node (ref "X4") (pin "12") (pinfunction "S_12") (pintype "passive"))
    )
    (net (code "128") (name "unconnected-(X5C-S-Pad11)") (class "Default")
      (node (ref "X5") (pin "11") (pinfunction "S_11") (pintype "passive"))
    )
    (net (code "129") (name "unconnected-(X5D-S-Pad12)") (class "Default")
      (node (ref "X5") (pin "12") (pinfunction "S_12") (pintype "passive"))
    )
  )
)
